# v2_0.net
KiCad netlist of a schematic drawn in EAGLE
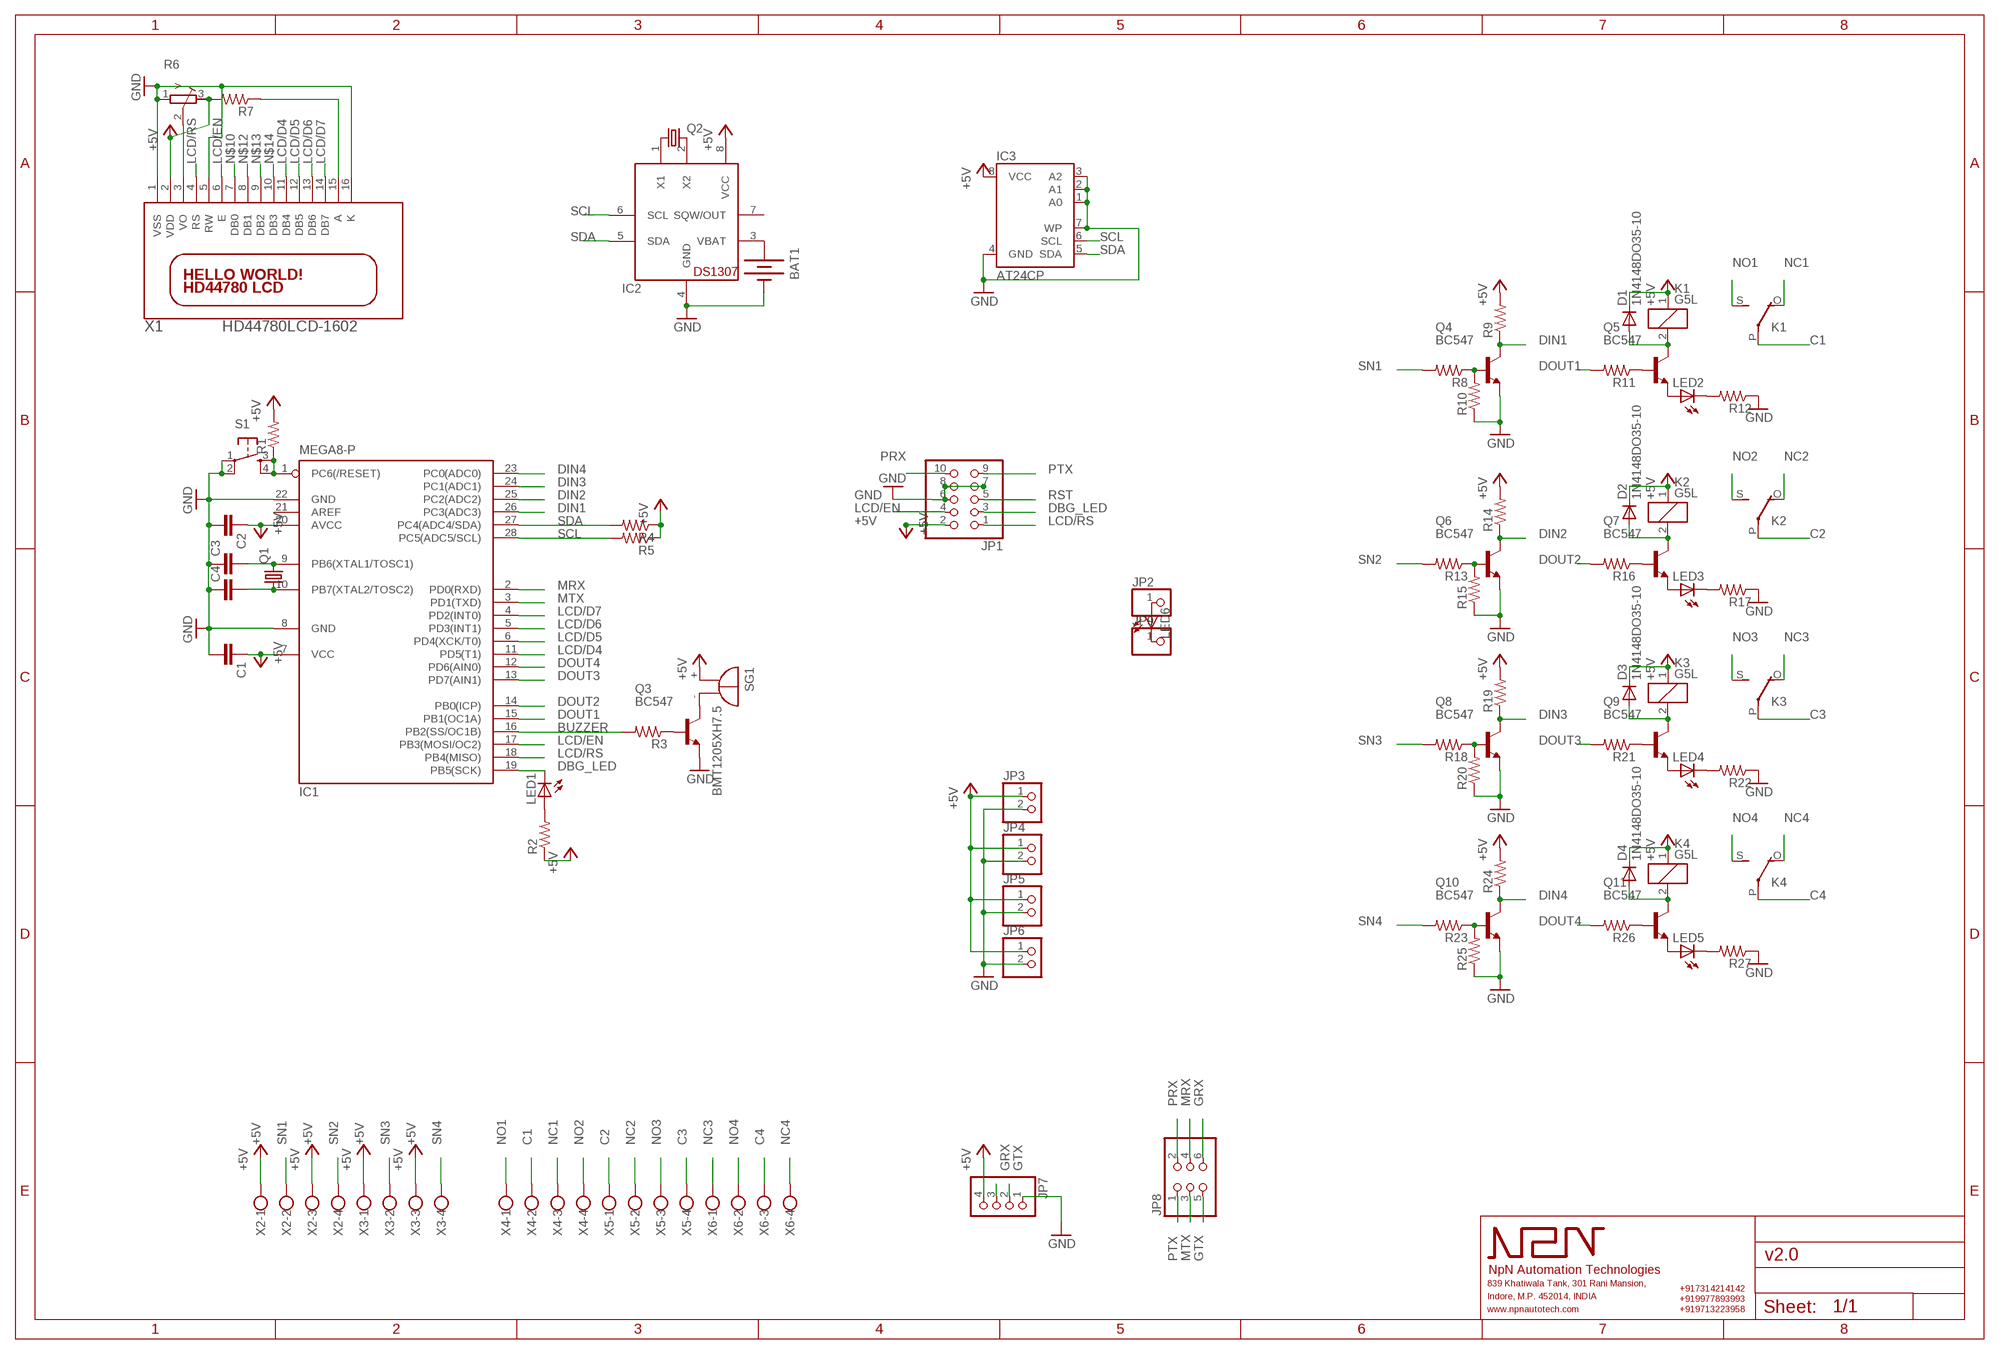
[diagram p0: schematic, sheet 1]

(export (version "E")
  (design (tool "Eeschema 10.0.6"))
  (components
    (comp (ref "BAT1")
      (value "BATTERY20PTH")
      (footprint "eagle-import:BATTCOM_20MM_PTH")
      (libsource (lib "eagle-import") (part "BATTERY20PTH"))
    )
    (comp (ref "C1")
      (value "C-EU050-025X075")
      (footprint "eagle-import:C050-025X075")
      (libsource (lib "eagle-import") (part "C-EU050-025X075"))
    )
    (comp (ref "C2")
      (value "C-EU050-025X075")
      (footprint "eagle-import:C050-025X075")
      (libsource (lib "eagle-import") (part "C-EU050-025X075"))
    )
    (comp (ref "C3")
      (value "C-EU050-025X075")
      (footprint "eagle-import:C050-025X075")
      (libsource (lib "eagle-import") (part "C-EU050-025X075"))
    )
    (comp (ref "C4")
      (value "C-EU050-025X075")
      (footprint "eagle-import:C050-025X075")
      (libsource (lib "eagle-import") (part "C-EU050-025X075"))
    )
    (comp (ref "D1")
      (value "1N4148DO35-10")
      (footprint "eagle-import:DO35-10")
      (libsource (lib "eagle-import") (part "1N4148DO35-10"))
    )
    (comp (ref "D2")
      (value "1N4148DO35-10")
      (footprint "eagle-import:DO35-10")
      (libsource (lib "eagle-import") (part "1N4148DO35-10"))
    )
    (comp (ref "D3")
      (value "1N4148DO35-10")
      (footprint "eagle-import:DO35-10")
      (libsource (lib "eagle-import") (part "1N4148DO35-10"))
    )
    (comp (ref "D4")
      (value "1N4148DO35-10")
      (footprint "eagle-import:DO35-10")
      (libsource (lib "eagle-import") (part "1N4148DO35-10"))
    )
    (comp (ref "IC1")
      (value "MEGA8-P")
      (footprint "eagle-import:DIL28-3")
      (libsource (lib "eagle-import") (part "MEGA8-P"))
    )
    (comp (ref "IC2")
      (value "DS1307")
      (footprint "eagle-import:DIL08")
      (libsource (lib "eagle-import") (part "DS1307"))
    )
    (comp (ref "IC3")
      (value "AT24CP")
      (footprint "eagle-import:DIL08")
      (fields (field (name "MPN") "AT24C1024BW-SH-B"))
      (libsource (lib "eagle-import") (part "AT24CP"))
    )
    (comp (ref "JP1")
      (value "PINHD-2X5")
      (footprint "eagle-import:2X05")
      (libsource (lib "eagle-import") (part "PINHD-2X5"))
    )
    (comp (ref "JP2")
      (value "PINHD-1X1")
      (footprint "eagle-import:1X01")
      (libsource (lib "eagle-import") (part "PINHD-1X1"))
    )
    (comp (ref "JP3")
      (value "PINHD-1X2")
      (footprint "eagle-import:1X02")
      (libsource (lib "eagle-import") (part "PINHD-1X2"))
    )
    (comp (ref "JP4")
      (value "PINHD-1X2")
      (footprint "eagle-import:1X02")
      (libsource (lib "eagle-import") (part "PINHD-1X2"))
    )
    (comp (ref "JP5")
      (value "PINHD-1X2")
      (footprint "eagle-import:1X02")
      (libsource (lib "eagle-import") (part "PINHD-1X2"))
    )
    (comp (ref "JP6")
      (value "PINHD-1X2")
      (footprint "eagle-import:1X02")
      (libsource (lib "eagle-import") (part "PINHD-1X2"))
    )
    (comp (ref "JP7")
      (value "PINHD-1X4")
      (footprint "eagle-import:1X04")
      (libsource (lib "eagle-import") (part "PINHD-1X4"))
    )
    (comp (ref "JP8")
      (value "PINHD-2X3")
      (footprint "eagle-import:2X03")
      (libsource (lib "eagle-import") (part "PINHD-2X3"))
    )
    (comp (ref "JP9")
      (value "PINHD-1X1")
      (footprint "eagle-import:1X01")
      (libsource (lib "eagle-import") (part "PINHD-1X1"))
    )
    (comp (ref "K1")
      (value "G5L")
      (footprint "eagle-import:G5LE")
      (libsource (lib "eagle-import") (part "G5L"))
    )
    (comp (ref "K2")
      (value "G5L")
      (footprint "eagle-import:G5LE")
      (libsource (lib "eagle-import") (part "G5L"))
    )
    (comp (ref "K3")
      (value "G5L")
      (footprint "eagle-import:G5LE")
      (libsource (lib "eagle-import") (part "G5L"))
    )
    (comp (ref "K4")
      (value "G5L")
      (footprint "eagle-import:G5LE")
      (libsource (lib "eagle-import") (part "G5L"))
    )
    (comp (ref "LED1")
      (value "LED5MM")
      (footprint "eagle-import:LED5MM")
      (libsource (lib "eagle-import") (part "LED5MM"))
    )
    (comp (ref "LED2")
      (value "LED5MM")
      (footprint "eagle-import:LED5MM")
      (libsource (lib "eagle-import") (part "LED5MM"))
    )
    (comp (ref "LED3")
      (value "LED5MM")
      (footprint "eagle-import:LED5MM")
      (libsource (lib "eagle-import") (part "LED5MM"))
    )
    (comp (ref "LED4")
      (value "LED5MM")
      (footprint "eagle-import:LED5MM")
      (libsource (lib "eagle-import") (part "LED5MM"))
    )
    (comp (ref "LED5")
      (value "LED5MM")
      (footprint "eagle-import:LED5MM")
      (libsource (lib "eagle-import") (part "LED5MM"))
    )
    (comp (ref "LED6")
      (value "LED5MM")
      (footprint "eagle-import:LED5MM")
      (libsource (lib "eagle-import") (part "LED5MM"))
    )
    (comp (ref "Q1")
      (value "CRYSTALHC49U-V")
      (footprint "eagle-import:HC49U-V")
      (libsource (lib "eagle-import") (part "CRYSTALHC49U-V"))
    )
    (comp (ref "Q2")
      (value "CRYSTALTC38H")
      (footprint "eagle-import:TC38H")
      (libsource (lib "eagle-import") (part "CRYSTALTC38H"))
    )
    (comp (ref "Q3")
      (value "BC547")
      (footprint "eagle-import:TO92")
      (libsource (lib "eagle-import") (part "BC547"))
    )
    (comp (ref "Q4")
      (value "BC547")
      (footprint "eagle-import:TO92")
      (libsource (lib "eagle-import") (part "BC547"))
    )
    (comp (ref "Q5")
      (value "BC547")
      (footprint "eagle-import:TO92")
      (libsource (lib "eagle-import") (part "BC547"))
    )
    (comp (ref "Q6")
      (value "BC547")
      (footprint "eagle-import:TO92")
      (libsource (lib "eagle-import") (part "BC547"))
    )
    (comp (ref "Q7")
      (value "BC547")
      (footprint "eagle-import:TO92")
      (libsource (lib "eagle-import") (part "BC547"))
    )
    (comp (ref "Q8")
      (value "BC547")
      (footprint "eagle-import:TO92")
      (libsource (lib "eagle-import") (part "BC547"))
    )
    (comp (ref "Q9")
      (value "BC547")
      (footprint "eagle-import:TO92")
      (libsource (lib "eagle-import") (part "BC547"))
    )
    (comp (ref "Q10")
      (value "BC547")
      (footprint "eagle-import:TO92")
      (libsource (lib "eagle-import") (part "BC547"))
    )
    (comp (ref "Q11")
      (value "BC547")
      (footprint "eagle-import:TO92")
      (libsource (lib "eagle-import") (part "BC547"))
    )
    (comp (ref "R1")
      (value "R-US_0207/10")
      (footprint "eagle-import:0207_10")
      (libsource (lib "eagle-import") (part "R-US_0207/10"))
    )
    (comp (ref "R2")
      (value "R-US_0207/10")
      (footprint "eagle-import:0207_10")
      (libsource (lib "eagle-import") (part "R-US_0207/10"))
    )
    (comp (ref "R3")
      (value "R-US_0207/10")
      (footprint "eagle-import:0207_10")
      (libsource (lib "eagle-import") (part "R-US_0207/10"))
    )
    (comp (ref "R4")
      (value "R-US_0207/10")
      (footprint "eagle-import:0207_10")
      (libsource (lib "eagle-import") (part "R-US_0207/10"))
    )
    (comp (ref "R5")
      (value "R-US_0207/10")
      (footprint "eagle-import:0207_10")
      (libsource (lib "eagle-import") (part "R-US_0207/10"))
    )
    (comp (ref "R6")
      (value "R-TRIMM3339P")
      (footprint "eagle-import:RTRIM3339P")
      (libsource (lib "eagle-import") (part "R-TRIMM3339P"))
    )
    (comp (ref "R7")
      (value "R-US_0207/10")
      (footprint "eagle-import:0207_10")
      (libsource (lib "eagle-import") (part "R-US_0207/10"))
    )
    (comp (ref "R8")
      (value "R-US_0207/10")
      (footprint "eagle-import:0207_10")
      (libsource (lib "eagle-import") (part "R-US_0207/10"))
    )
    (comp (ref "R9")
      (value "R-US_0207/10")
      (footprint "eagle-import:0207_10")
      (libsource (lib "eagle-import") (part "R-US_0207/10"))
    )
    (comp (ref "R10")
      (value "R-US_0207/10")
      (footprint "eagle-import:0207_10")
      (libsource (lib "eagle-import") (part "R-US_0207/10"))
    )
    (comp (ref "R11")
      (value "R-US_0207/10")
      (footprint "eagle-import:0207_10")
      (libsource (lib "eagle-import") (part "R-US_0207/10"))
    )
    (comp (ref "R12")
      (value "R-US_0207/10")
      (footprint "eagle-import:0207_10")
      (libsource (lib "eagle-import") (part "R-US_0207/10"))
    )
    (comp (ref "R13")
      (value "R-US_0207/10")
      (footprint "eagle-import:0207_10")
      (libsource (lib "eagle-import") (part "R-US_0207/10"))
    )
    (comp (ref "R14")
      (value "R-US_0207/10")
      (footprint "eagle-import:0207_10")
      (libsource (lib "eagle-import") (part "R-US_0207/10"))
    )
    (comp (ref "R15")
      (value "R-US_0207/10")
      (footprint "eagle-import:0207_10")
      (libsource (lib "eagle-import") (part "R-US_0207/10"))
    )
    (comp (ref "R16")
      (value "R-US_0207/10")
      (footprint "eagle-import:0207_10")
      (libsource (lib "eagle-import") (part "R-US_0207/10"))
    )
    (comp (ref "R17")
      (value "R-US_0207/10")
      (footprint "eagle-import:0207_10")
      (libsource (lib "eagle-import") (part "R-US_0207/10"))
    )
    (comp (ref "R18")
      (value "R-US_0207/10")
      (footprint "eagle-import:0207_10")
      (libsource (lib "eagle-import") (part "R-US_0207/10"))
    )
    (comp (ref "R19")
      (value "R-US_0207/10")
      (footprint "eagle-import:0207_10")
      (libsource (lib "eagle-import") (part "R-US_0207/10"))
    )
    (comp (ref "R20")
      (value "R-US_0207/10")
      (footprint "eagle-import:0207_10")
      (libsource (lib "eagle-import") (part "R-US_0207/10"))
    )
    (comp (ref "R21")
      (value "R-US_0207/10")
      (footprint "eagle-import:0207_10")
      (libsource (lib "eagle-import") (part "R-US_0207/10"))
    )
    (comp (ref "R22")
      (value "R-US_0207/10")
      (footprint "eagle-import:0207_10")
      (libsource (lib "eagle-import") (part "R-US_0207/10"))
    )
    (comp (ref "R23")
      (value "R-US_0207/10")
      (footprint "eagle-import:0207_10")
      (libsource (lib "eagle-import") (part "R-US_0207/10"))
    )
    (comp (ref "R24")
      (value "R-US_0207/10")
      (footprint "eagle-import:0207_10")
      (libsource (lib "eagle-import") (part "R-US_0207/10"))
    )
    (comp (ref "R25")
      (value "R-US_0207/10")
      (footprint "eagle-import:0207_10")
      (libsource (lib "eagle-import") (part "R-US_0207/10"))
    )
    (comp (ref "R26")
      (value "R-US_0207/10")
      (footprint "eagle-import:0207_10")
      (libsource (lib "eagle-import") (part "R-US_0207/10"))
    )
    (comp (ref "R27")
      (value "R-US_0207/10")
      (footprint "eagle-import:0207_10")
      (libsource (lib "eagle-import") (part "R-US_0207/10"))
    )
    (comp (ref "S1")
      (value "TAC_SWITCHPTH")
      (footprint "eagle-import:TACTILE-PTH")
      (libsource (lib "eagle-import") (part "TAC_SWITCHPTH"))
    )
    (comp (ref "SG1")
      (value "BMT1205XH7.5")
      (footprint "eagle-import:BMT1205XH7.5")
      (libsource (lib "eagle-import") (part "BMT1205XH7.5"))
    )
    (comp (ref "X1")
      (value "HD44780LCD-1602")
      (footprint "eagle-import:LCD1602")
      (libsource (lib "eagle-import") (part "HD44780LCD-1602"))
    )
    (comp (ref "X2")
      (value "W237-4")
      (footprint "eagle-import:W237-4")
      (libsource (lib "eagle-import") (part "W237-4"))
    )
    (comp (ref "X3")
      (value "W237-4")
      (footprint "eagle-import:W237-4")
      (libsource (lib "eagle-import") (part "W237-4"))
    )
    (comp (ref "X4")
      (value "W237-4")
      (footprint "eagle-import:W237-4")
      (libsource (lib "eagle-import") (part "W237-4"))
    )
    (comp (ref "X5")
      (value "W237-4")
      (footprint "eagle-import:W237-4")
      (libsource (lib "eagle-import") (part "W237-4"))
    )
    (comp (ref "X6")
      (value "W237-4")
      (footprint "eagle-import:W237-4")
      (libsource (lib "eagle-import") (part "W237-4"))
    )
  )
  (nets
    (net (code "1") (name "+5V") (class "Default")
      (node (ref "C1") (pin "1") (pinfunction "1_1") (pintype "passive"))
      (node (ref "C2") (pin "1") (pinfunction "1_1") (pintype "passive"))
      (node (ref "D1") (pin "C") (pinfunction "C_C") (pintype "passive"))
      (node (ref "D2") (pin "C") (pinfunction "C_C") (pintype "passive"))
      (node (ref "D3") (pin "C") (pinfunction "C_C") (pintype "passive"))
      (node (ref "D4") (pin "C") (pinfunction "C_C") (pintype "passive"))
      (node (ref "IC1") (pin "20") (pinfunction "AVCC_20") (pintype "power_in"))
      (node (ref "IC1") (pin "7") (pinfunction "VCC_7") (pintype "power_in"))
      (node (ref "IC2") (pin "8") (pinfunction "VCC_8") (pintype "power_in"))
      (node (ref "IC3") (pin "8") (pinfunction "VCC_8") (pintype "power_in"))
      (node (ref "JP1") (pin "2") (pinfunction "2_2") (pintype "passive"))
      (node (ref "JP3") (pin "1") (pinfunction "1_1") (pintype "passive"))
      (node (ref "JP4") (pin "1") (pinfunction "1_1") (pintype "passive"))
      (node (ref "JP5") (pin "1") (pinfunction "1_1") (pintype "passive"))
      (node (ref "JP6") (pin "1") (pinfunction "1_1") (pintype "passive"))
      (node (ref "JP7") (pin "4") (pinfunction "4_4") (pintype "passive"))
      (node (ref "K1") (pin "1") (pinfunction "1_1") (pintype "passive"))
      (node (ref "K2") (pin "1") (pinfunction "1_1") (pintype "passive"))
      (node (ref "K3") (pin "1") (pinfunction "1_1") (pintype "passive"))
      (node (ref "K4") (pin "1") (pinfunction "1_1") (pintype "passive"))
      (node (ref "R1") (pin "2") (pinfunction "2_2") (pintype "passive"))
      (node (ref "R14") (pin "2") (pinfunction "2_2") (pintype "passive"))
      (node (ref "R19") (pin "2") (pinfunction "2_2") (pintype "passive"))
      (node (ref "R2") (pin "1") (pinfunction "1_1") (pintype "passive"))
      (node (ref "R24") (pin "2") (pinfunction "2_2") (pintype "passive"))
      (node (ref "R4") (pin "1") (pinfunction "1_1") (pintype "passive"))
      (node (ref "R5") (pin "1") (pinfunction "1_1") (pintype "passive"))
      (node (ref "R6") (pin "3") (pinfunction "E_3") (pintype "passive"))
      (node (ref "R7") (pin "2") (pinfunction "2_2") (pintype "passive"))
      (node (ref "R9") (pin "2") (pinfunction "2_2") (pintype "passive"))
      (node (ref "SG1") (pin "+") (pinfunction "+_+") (pintype "passive"))
      (node (ref "X1") (pin "2") (pinfunction "VDD_2") (pintype "power_in"))
      (node (ref "X2") (pin "1") (pinfunction "KL_1") (pintype "passive"))
      (node (ref "X2") (pin "3") (pinfunction "KL_3") (pintype "passive"))
      (node (ref "X3") (pin "1") (pinfunction "KL_1") (pintype "passive"))
      (node (ref "X3") (pin "3") (pinfunction "KL_3") (pintype "passive"))
    )
    (net (code "2") (name "/BUZZER") (class "Default")
      (node (ref "IC1") (pin "16") (pinfunction "PB2(SS/OC1B)_16") (pintype "bidirectional"))
      (node (ref "R3") (pin "2") (pinfunction "2_2") (pintype "passive"))
    )
    (net (code "3") (name "/C1") (class "Default")
      (node (ref "K1") (pin "P") (pinfunction "P_P") (pintype "passive"))
      (node (ref "X4") (pin "2") (pinfunction "KL_2") (pintype "passive"))
    )
    (net (code "4") (name "/C2") (class "Default")
      (node (ref "K2") (pin "P") (pinfunction "P_P") (pintype "passive"))
      (node (ref "X5") (pin "1") (pinfunction "KL_1") (pintype "passive"))
    )
    (net (code "5") (name "/C3") (class "Default")
      (node (ref "K3") (pin "P") (pinfunction "P_P") (pintype "passive"))
      (node (ref "X5") (pin "4") (pinfunction "KL_4") (pintype "passive"))
    )
    (net (code "6") (name "/C4") (class "Default")
      (node (ref "K4") (pin "P") (pinfunction "P_P") (pintype "passive"))
      (node (ref "X6") (pin "3") (pinfunction "KL_3") (pintype "passive"))
    )
    (net (code "7") (name "/DBG_LED") (class "Default")
      (node (ref "IC1") (pin "19") (pinfunction "PB5(SCK)_19") (pintype "bidirectional"))
      (node (ref "JP1") (pin "3") (pinfunction "3_3") (pintype "passive"))
      (node (ref "LED1") (pin "K") (pinfunction "C_K") (pintype "passive"))
    )
    (net (code "8") (name "/DIN1") (class "Default")
      (node (ref "IC1") (pin "26") (pinfunction "PC3(ADC3)_26") (pintype "bidirectional"))
      (node (ref "Q4") (pin "3") (pinfunction "C_3") (pintype "passive"))
      (node (ref "R9") (pin "1") (pinfunction "1_1") (pintype "passive"))
    )
    (net (code "9") (name "/DIN2") (class "Default")
      (node (ref "IC1") (pin "25") (pinfunction "PC2(ADC2)_25") (pintype "bidirectional"))
      (node (ref "Q6") (pin "3") (pinfunction "C_3") (pintype "passive"))
      (node (ref "R14") (pin "1") (pinfunction "1_1") (pintype "passive"))
    )
    (net (code "10") (name "/DIN3") (class "Default")
      (node (ref "IC1") (pin "24") (pinfunction "PC1(ADC1)_24") (pintype "bidirectional"))
      (node (ref "Q8") (pin "3") (pinfunction "C_3") (pintype "passive"))
      (node (ref "R19") (pin "1") (pinfunction "1_1") (pintype "passive"))
    )
    (net (code "11") (name "/DIN4") (class "Default")
      (node (ref "IC1") (pin "23") (pinfunction "PC0(ADC0)_23") (pintype "bidirectional"))
      (node (ref "Q10") (pin "3") (pinfunction "C_3") (pintype "passive"))
      (node (ref "R24") (pin "1") (pinfunction "1_1") (pintype "passive"))
    )
    (net (code "12") (name "/DOUT1") (class "Default")
      (node (ref "IC1") (pin "15") (pinfunction "PB1(OC1A)_15") (pintype "bidirectional"))
      (node (ref "R11") (pin "2") (pinfunction "2_2") (pintype "passive"))
    )
    (net (code "13") (name "/DOUT2") (class "Default")
      (node (ref "IC1") (pin "14") (pinfunction "PB0(ICP)_14") (pintype "bidirectional"))
      (node (ref "R16") (pin "2") (pinfunction "2_2") (pintype "passive"))
    )
    (net (code "14") (name "/DOUT3") (class "Default")
      (node (ref "IC1") (pin "13") (pinfunction "PD7(AIN1)_13") (pintype "bidirectional"))
      (node (ref "R21") (pin "2") (pinfunction "2_2") (pintype "passive"))
    )
    (net (code "15") (name "/DOUT4") (class "Default")
      (node (ref "IC1") (pin "12") (pinfunction "PD6(AIN0)_12") (pintype "bidirectional"))
      (node (ref "R26") (pin "2") (pinfunction "2_2") (pintype "passive"))
    )
    (net (code "16") (name "/GRX") (class "Default")
      (node (ref "JP7") (pin "3") (pinfunction "3_3") (pintype "passive"))
      (node (ref "JP8") (pin "6") (pinfunction "6_6") (pintype "passive"))
    )
    (net (code "17") (name "/GTX") (class "Default")
      (node (ref "JP7") (pin "2") (pinfunction "2_2") (pintype "passive"))
      (node (ref "JP8") (pin "5") (pinfunction "5_5") (pintype "passive"))
    )
    (net (code "18") (name "/LCD{slash}D4") (class "Default")
      (node (ref "IC1") (pin "11") (pinfunction "PD5(T1)_11") (pintype "bidirectional"))
      (node (ref "X1") (pin "11") (pinfunction "DB4_11") (pintype "bidirectional"))
    )
    (net (code "19") (name "/LCD{slash}D5") (class "Default")
      (node (ref "IC1") (pin "6") (pinfunction "PD4(XCK/T0)_6") (pintype "bidirectional"))
      (node (ref "X1") (pin "12") (pinfunction "DB5_12") (pintype "bidirectional"))
    )
    (net (code "20") (name "/LCD{slash}D6") (class "Default")
      (node (ref "IC1") (pin "5") (pinfunction "PD3(INT1)_5") (pintype "bidirectional"))
      (node (ref "X1") (pin "13") (pinfunction "DB6_13") (pintype "bidirectional"))
    )
    (net (code "21") (name "/LCD{slash}D7") (class "Default")
      (node (ref "IC1") (pin "4") (pinfunction "PD2(INT0)_4") (pintype "bidirectional"))
      (node (ref "X1") (pin "14") (pinfunction "DB7_14") (pintype "bidirectional"))
    )
    (net (code "22") (name "/LCD{slash}EN") (class "Default")
      (node (ref "IC1") (pin "17") (pinfunction "PB3(MOSI/OC2)_17") (pintype "bidirectional"))
      (node (ref "JP1") (pin "4") (pinfunction "4_4") (pintype "passive"))
      (node (ref "X1") (pin "6") (pinfunction "E_6") (pintype "input"))
    )
    (net (code "23") (name "/LCD{slash}RS") (class "Default")
      (node (ref "IC1") (pin "18") (pinfunction "PB4(MISO)_18") (pintype "bidirectional"))
      (node (ref "JP1") (pin "1") (pinfunction "1_1") (pintype "passive"))
      (node (ref "X1") (pin "4") (pinfunction "RS_4") (pintype "input"))
    )
    (net (code "24") (name "/MRX") (class "Default")
      (node (ref "IC1") (pin "2") (pinfunction "PD0(RXD)_2") (pintype "bidirectional"))
      (node (ref "JP8") (pin "4") (pinfunction "4_4") (pintype "passive"))
    )
    (net (code "25") (name "/MTX") (class "Default")
      (node (ref "IC1") (pin "3") (pinfunction "PD1(TXD)_3") (pintype "bidirectional"))
      (node (ref "JP8") (pin "3") (pinfunction "3_3") (pintype "passive"))
    )
    (net (code "26") (name "/N$10") (class "Default")
      (node (ref "X1") (pin "7") (pinfunction "DB0_7") (pintype "bidirectional"))
    )
    (net (code "27") (name "/N$12") (class "Default")
      (node (ref "X1") (pin "8") (pinfunction "DB1_8") (pintype "bidirectional"))
    )
    (net (code "28") (name "/N$13") (class "Default")
      (node (ref "X1") (pin "9") (pinfunction "DB2_9") (pintype "bidirectional"))
    )
    (net (code "29") (name "/N$14") (class "Default")
      (node (ref "X1") (pin "10") (pinfunction "DB3_10") (pintype "bidirectional"))
    )
    (net (code "30") (name "/NC1") (class "Default")
      (node (ref "K1") (pin "O") (pinfunction "O_O") (pintype "passive"))
      (node (ref "X4") (pin "3") (pinfunction "KL_3") (pintype "passive"))
    )
    (net (code "31") (name "/NC2") (class "Default")
      (node (ref "K2") (pin "O") (pinfunction "O_O") (pintype "passive"))
      (node (ref "X5") (pin "2") (pinfunction "KL_2") (pintype "passive"))
    )
    (net (code "32") (name "/NC3") (class "Default")
      (node (ref "K3") (pin "O") (pinfunction "O_O") (pintype "passive"))
      (node (ref "X6") (pin "1") (pinfunction "KL_1") (pintype "passive"))
    )
    (net (code "33") (name "/NC4") (class "Default")
      (node (ref "K4") (pin "O") (pinfunction "O_O") (pintype "passive"))
      (node (ref "X6") (pin "4") (pinfunction "KL_4") (pintype "passive"))
    )
    (net (code "34") (name "/NO1") (class "Default")
      (node (ref "K1") (pin "S") (pinfunction "S_S") (pintype "passive"))
      (node (ref "X4") (pin "1") (pinfunction "KL_1") (pintype "passive"))
    )
    (net (code "35") (name "/NO2") (class "Default")
      (node (ref "K2") (pin "S") (pinfunction "S_S") (pintype "passive"))
      (node (ref "X4") (pin "4") (pinfunction "KL_4") (pintype "passive"))
    )
    (net (code "36") (name "/NO3") (class "Default")
      (node (ref "K3") (pin "S") (pinfunction "S_S") (pintype "passive"))
      (node (ref "X5") (pin "3") (pinfunction "KL_3") (pintype "passive"))
    )
    (net (code "37") (name "/NO4") (class "Default")
      (node (ref "K4") (pin "S") (pinfunction "S_S") (pintype "passive"))
      (node (ref "X6") (pin "2") (pinfunction "KL_2") (pintype "passive"))
    )
    (net (code "38") (name "/PRX") (class "Default")
      (node (ref "JP1") (pin "10") (pinfunction "10_10") (pintype "passive"))
      (node (ref "JP8") (pin "2") (pinfunction "2_2") (pintype "passive"))
    )
    (net (code "39") (name "/PTX") (class "Default")
      (node (ref "JP1") (pin "9") (pinfunction "9_9") (pintype "passive"))
      (node (ref "JP8") (pin "1") (pinfunction "1_1") (pintype "passive"))
    )
    (net (code "40") (name "/RST") (class "Default")
      (node (ref "IC1") (pin "1") (pinfunction "PC6(/RESET)_1") (pintype "bidirectional"))
      (node (ref "JP1") (pin "5") (pinfunction "5_5") (pintype "passive"))
      (node (ref "R1") (pin "1") (pinfunction "1_1") (pintype "passive"))
      (node (ref "S1") (pin "3") (pinfunction "3_3") (pintype "passive"))
      (node (ref "S1") (pin "4") (pinfunction "4_4") (pintype "passive"))
    )
    (net (code "41") (name "/SCL") (class "Default")
      (node (ref "IC1") (pin "28") (pinfunction "PC5(ADC5/SCL)_28") (pintype "bidirectional"))
      (node (ref "IC2") (pin "6") (pinfunction "SCL_6") (pintype "bidirectional"))
      (node (ref "IC3") (pin "6") (pinfunction "SCL_6") (pintype "bidirectional"))
      (node (ref "R5") (pin "2") (pinfunction "2_2") (pintype "passive"))
    )
    (net (code "42") (name "/SDA") (class "Default")
      (node (ref "IC1") (pin "27") (pinfunction "PC4(ADC4/SDA)_27") (pintype "bidirectional"))
      (node (ref "IC2") (pin "5") (pinfunction "SDA_5") (pintype "bidirectional"))
      (node (ref "IC3") (pin "5") (pinfunction "SDA_5") (pintype "bidirectional"))
      (node (ref "R4") (pin "2") (pinfunction "2_2") (pintype "passive"))
    )
    (net (code "43") (name "/SN1") (class "Default")
      (node (ref "R8") (pin "2") (pinfunction "2_2") (pintype "passive"))
      (node (ref "X2") (pin "2") (pinfunction "KL_2") (pintype "passive"))
    )
    (net (code "44") (name "/SN2") (class "Default")
      (node (ref "R13") (pin "2") (pinfunction "2_2") (pintype "passive"))
      (node (ref "X2") (pin "4") (pinfunction "KL_4") (pintype "passive"))
    )
    (net (code "45") (name "/SN3") (class "Default")
      (node (ref "R18") (pin "2") (pinfunction "2_2") (pintype "passive"))
      (node (ref "X3") (pin "2") (pinfunction "KL_2") (pintype "passive"))
    )
    (net (code "46") (name "/SN4") (class "Default")
      (node (ref "R23") (pin "2") (pinfunction "2_2") (pintype "passive"))
      (node (ref "X3") (pin "4") (pinfunction "KL_4") (pintype "passive"))
    )
    (net (code "47") (name "GND") (class "Default")
      (node (ref "BAT1") (pin "2") (pinfunction "-_2") (pintype "power_in"))
      (node (ref "C1") (pin "2") (pinfunction "2_2") (pintype "passive"))
      (node (ref "C2") (pin "2") (pinfunction "2_2") (pintype "passive"))
      (node (ref "C3") (pin "1") (pinfunction "1_1") (pintype "passive"))
      (node (ref "C4") (pin "1") (pinfunction "1_1") (pintype "passive"))
      (node (ref "IC1") (pin "22") (pinfunction "GND_22") (pintype "power_in"))
      (node (ref "IC1") (pin "8") (pinfunction "GND_8") (pintype "power_in"))
      (node (ref "IC2") (pin "4") (pinfunction "GND_4") (pintype "power_in"))
      (node (ref "IC3") (pin "1") (pinfunction "A0_1") (pintype "input"))
      (node (ref "IC3") (pin "2") (pinfunction "A1_2") (pintype "input"))
      (node (ref "IC3") (pin "3") (pinfunction "A2_3") (pintype "input"))
      (node (ref "IC3") (pin "4") (pinfunction "GND_4") (pintype "power_in"))
      (node (ref "IC3") (pin "7") (pinfunction "WP_7") (pintype "input"))
      (node (ref "JP1") (pin "6") (pinfunction "6_6") (pintype "passive"))
      (node (ref "JP1") (pin "7") (pinfunction "7_7") (pintype "passive"))
      (node (ref "JP1") (pin "8") (pinfunction "8_8") (pintype "passive"))
      (node (ref "JP3") (pin "2") (pinfunction "2_2") (pintype "passive"))
      (node (ref "JP4") (pin "2") (pinfunction "2_2") (pintype "passive"))
      (node (ref "JP5") (pin "2") (pinfunction "2_2") (pintype "passive"))
      (node (ref "JP6") (pin "2") (pinfunction "2_2") (pintype "passive"))
      (node (ref "JP7") (pin "1") (pinfunction "1_1") (pintype "passive"))
      (node (ref "Q10") (pin "1") (pinfunction "E_1") (pintype "passive"))
      (node (ref "Q3") (pin "1") (pinfunction "E_1") (pintype "passive"))
      (node (ref "Q4") (pin "1") (pinfunction "E_1") (pintype "passive"))
      (node (ref "Q6") (pin "1") (pinfunction "E_1") (pintype "passive"))
      (node (ref "Q8") (pin "1") (pinfunction "E_1") (pintype "passive"))
      (node (ref "R10") (pin "1") (pinfunction "1_1") (pintype "passive"))
      (node (ref "R12") (pin "1") (pinfunction "1_1") (pintype "passive"))
      (node (ref "R15") (pin "1") (pinfunction "1_1") (pintype "passive"))
      (node (ref "R17") (pin "1") (pinfunction "1_1") (pintype "passive"))
      (node (ref "R20") (pin "1") (pinfunction "1_1") (pintype "passive"))
      (node (ref "R22") (pin "1") (pinfunction "1_1") (pintype "passive"))
      (node (ref "R25") (pin "1") (pinfunction "1_1") (pintype "passive"))
      (node (ref "R27") (pin "1") (pinfunction "1_1") (pintype "passive"))
      (node (ref "R6") (pin "1") (pinfunction "A_1") (pintype "passive"))
      (node (ref "S1") (pin "1") (pinfunction "1_1") (pintype "passive"))
      (node (ref "S1") (pin "2") (pinfunction "2_2") (pintype "passive"))
      (node (ref "X1") (pin "1") (pinfunction "VSS_1") (pintype "power_in"))
      (node (ref "X1") (pin "16") (pinfunction "K_16") (pintype "input"))
      (node (ref "X1") (pin "5") (pinfunction "RW_5") (pintype "input"))
    )
    (net (code "48") (name "Net-(BAT1-+)") (class "Default")
      (node (ref "BAT1") (pin "1") (pinfunction "+_1") (pintype "power_in"))
      (node (ref "IC2") (pin "3") (pinfunction "VBAT_3") (pintype "power_in"))
    )
    (net (code "49") (name "Net-(IC1-PB6(XTAL1{slash}TOSC1))") (class "Default")
      (node (ref "C3") (pin "2") (pinfunction "2_2") (pintype "passive"))
      (node (ref "IC1") (pin "9") (pinfunction "PB6(XTAL1/TOSC1)_9") (pintype "bidirectional"))
      (node (ref "Q1") (pin "2") (pinfunction "2_2") (pintype "passive"))
    )
    (net (code "50") (name "Net-(IC1-PB7(XTAL2{slash}TOSC2))") (class "Default")
      (node (ref "C4") (pin "2") (pinfunction "2_2") (pintype "passive"))
      (node (ref "IC1") (pin "10") (pinfunction "PB7(XTAL2/TOSC2)_10") (pintype "bidirectional"))
      (node (ref "Q1") (pin "1") (pinfunction "1_1") (pintype "passive"))
    )
    (net (code "51") (name "Net-(IC2-X1)") (class "Default")
      (node (ref "IC2") (pin "1") (pinfunction "X1_1") (pintype "passive"))
      (node (ref "Q2") (pin "1") (pinfunction "1_1") (pintype "passive"))
    )
    (net (code "52") (name "Net-(IC2-X2)") (class "Default")
      (node (ref "IC2") (pin "2") (pinfunction "X2_2") (pintype "passive"))
      (node (ref "Q2") (pin "2") (pinfunction "2_2") (pintype "passive"))
    )
    (net (code "53") (name "Net-(JP2-Pad1)") (class "Default")
      (node (ref "JP2") (pin "1") (pinfunction "1_1") (pintype "passive"))
      (node (ref "LED6") (pin "A") (pinfunction "A_A") (pintype "passive"))
    )
    (net (code "54") (name "Net-(LED1-PadA)") (class "Default")
      (node (ref "LED1") (pin "A") (pinfunction "A_A") (pintype "passive"))
      (node (ref "R2") (pin "2") (pinfunction "2_2") (pintype "passive"))
    )
    (net (code "55") (name "Net-(LED2-C)") (class "Default")
      (node (ref "LED2") (pin "K") (pinfunction "C_K") (pintype "passive"))
      (node (ref "R12") (pin "2") (pinfunction "2_2") (pintype "passive"))
    )
    (net (code "56") (name "Net-(LED3-C)") (class "Default")
      (node (ref "LED3") (pin "K") (pinfunction "C_K") (pintype "passive"))
      (node (ref "R17") (pin "2") (pinfunction "2_2") (pintype "passive"))
    )
    (net (code "57") (name "Net-(LED4-C)") (class "Default")
      (node (ref "LED4") (pin "K") (pinfunction "C_K") (pintype "passive"))
      (node (ref "R22") (pin "2") (pinfunction "2_2") (pintype "passive"))
    )
    (net (code "58") (name "Net-(LED5-C)") (class "Default")
      (node (ref "LED5") (pin "K") (pinfunction "C_K") (pintype "passive"))
      (node (ref "R27") (pin "2") (pinfunction "2_2") (pintype "passive"))
    )
    (net (code "59") (name "Net-(LED6-C)") (class "Default")
      (node (ref "JP9") (pin "1") (pinfunction "1_1") (pintype "passive"))
      (node (ref "LED6") (pin "K") (pinfunction "C_K") (pintype "passive"))
    )
    (net (code "60") (name "Net-(Q3-B)") (class "Default")
      (node (ref "Q3") (pin "2") (pinfunction "B_2") (pintype "passive"))
      (node (ref "R3") (pin "1") (pinfunction "1_1") (pintype "passive"))
    )
    (net (code "61") (name "Net-(Q3-C)") (class "Default")
      (node (ref "Q3") (pin "3") (pinfunction "C_3") (pintype "passive"))
      (node (ref "SG1") (pin "-") (pinfunction "-_-") (pintype "passive"))
    )
    (net (code "62") (name "Net-(Q4-B)") (class "Default")
      (node (ref "Q4") (pin "2") (pinfunction "B_2") (pintype "passive"))
      (node (ref "R10") (pin "2") (pinfunction "2_2") (pintype "passive"))
      (node (ref "R8") (pin "1") (pinfunction "1_1") (pintype "passive"))
    )
    (net (code "63") (name "Net-(Q5-B)") (class "Default")
      (node (ref "Q5") (pin "2") (pinfunction "B_2") (pintype "passive"))
      (node (ref "R11") (pin "1") (pinfunction "1_1") (pintype "passive"))
    )
    (net (code "64") (name "Net-(Q5-C)") (class "Default")
      (node (ref "D1") (pin "A") (pinfunction "A_A") (pintype "passive"))
      (node (ref "K1") (pin "2") (pinfunction "2_2") (pintype "passive"))
      (node (ref "Q5") (pin "3") (pinfunction "C_3") (pintype "passive"))
    )
    (net (code "65") (name "Net-(Q5-E)") (class "Default")
      (node (ref "LED2") (pin "A") (pinfunction "A_A") (pintype "passive"))
      (node (ref "Q5") (pin "1") (pinfunction "E_1") (pintype "passive"))
    )
    (net (code "66") (name "Net-(Q6-B)") (class "Default")
      (node (ref "Q6") (pin "2") (pinfunction "B_2") (pintype "passive"))
      (node (ref "R13") (pin "1") (pinfunction "1_1") (pintype "passive"))
      (node (ref "R15") (pin "2") (pinfunction "2_2") (pintype "passive"))
    )
    (net (code "67") (name "Net-(Q7-B)") (class "Default")
      (node (ref "Q7") (pin "2") (pinfunction "B_2") (pintype "passive"))
      (node (ref "R16") (pin "1") (pinfunction "1_1") (pintype "passive"))
    )
    (net (code "68") (name "Net-(Q7-C)") (class "Default")
      (node (ref "D2") (pin "A") (pinfunction "A_A") (pintype "passive"))
      (node (ref "K2") (pin "2") (pinfunction "2_2") (pintype "passive"))
      (node (ref "Q7") (pin "3") (pinfunction "C_3") (pintype "passive"))
    )
    (net (code "69") (name "Net-(Q7-E)") (class "Default")
      (node (ref "LED3") (pin "A") (pinfunction "A_A") (pintype "passive"))
      (node (ref "Q7") (pin "1") (pinfunction "E_1") (pintype "passive"))
    )
    (net (code "70") (name "Net-(Q8-B)") (class "Default")
      (node (ref "Q8") (pin "2") (pinfunction "B_2") (pintype "passive"))
      (node (ref "R18") (pin "1") (pinfunction "1_1") (pintype "passive"))
      (node (ref "R20") (pin "2") (pinfunction "2_2") (pintype "passive"))
    )
    (net (code "71") (name "Net-(Q9-B)") (class "Default")
      (node (ref "Q9") (pin "2") (pinfunction "B_2") (pintype "passive"))
      (node (ref "R21") (pin "1") (pinfunction "1_1") (pintype "passive"))
    )
    (net (code "72") (name "Net-(Q9-C)") (class "Default")
      (node (ref "D3") (pin "A") (pinfunction "A_A") (pintype "passive"))
      (node (ref "K3") (pin "2") (pinfunction "2_2") (pintype "passive"))
      (node (ref "Q9") (pin "3") (pinfunction "C_3") (pintype "passive"))
    )
    (net (code "73") (name "Net-(Q9-E)") (class "Default")
      (node (ref "LED4") (pin "A") (pinfunction "A_A") (pintype "passive"))
      (node (ref "Q9") (pin "1") (pinfunction "E_1") (pintype "passive"))
    )
    (net (code "74") (name "Net-(Q10-B)") (class "Default")
      (node (ref "Q10") (pin "2") (pinfunction "B_2") (pintype "passive"))
      (node (ref "R23") (pin "1") (pinfunction "1_1") (pintype "passive"))
      (node (ref "R25") (pin "2") (pinfunction "2_2") (pintype "passive"))
    )
    (net (code "75") (name "Net-(Q11-B)") (class "Default")
      (node (ref "Q11") (pin "2") (pinfunction "B_2") (pintype "passive"))
      (node (ref "R26") (pin "1") (pinfunction "1_1") (pintype "passive"))
    )
    (net (code "76") (name "Net-(Q11-C)") (class "Default")
      (node (ref "D4") (pin "A") (pinfunction "A_A") (pintype "passive"))
      (node (ref "K4") (pin "2") (pinfunction "2_2") (pintype "passive"))
      (node (ref "Q11") (pin "3") (pinfunction "C_3") (pintype "passive"))
    )
    (net (code "77") (name "Net-(Q11-E)") (class "Default")
      (node (ref "LED5") (pin "A") (pinfunction "A_A") (pintype "passive"))
      (node (ref "Q11") (pin "1") (pinfunction "E_1") (pintype "passive"))
    )
    (net (code "78") (name "Net-(R6-S)") (class "Default")
      (node (ref "R6") (pin "2") (pinfunction "S_2") (pintype "passive"))
      (node (ref "X1") (pin "3") (pinfunction "VO_3") (pintype "input"))
    )
    (net (code "79") (name "Net-(X1-A)") (class "Default")
      (node (ref "R7") (pin "1") (pinfunction "1_1") (pintype "passive"))
      (node (ref "X1") (pin "15") (pinfunction "A_15") (pintype "input"))
    )
    (net (code "80") (name "unconnected-(IC1-AREF-Pad21)") (class "Default")
      (node (ref "IC1") (pin "21") (pinfunction "AREF_21") (pintype "passive"))
    )
    (net (code "81") (name "unconnected-(IC2-SQW{slash}OUT-Pad7)") (class "Default")
      (node (ref "IC2") (pin "7") (pinfunction "SQW/OUT_7") (pintype "bidirectional"))
    )
  )
)
